# USB_Isolator_v001.net
KiCad netlist of a schematic drawn in EAGLE
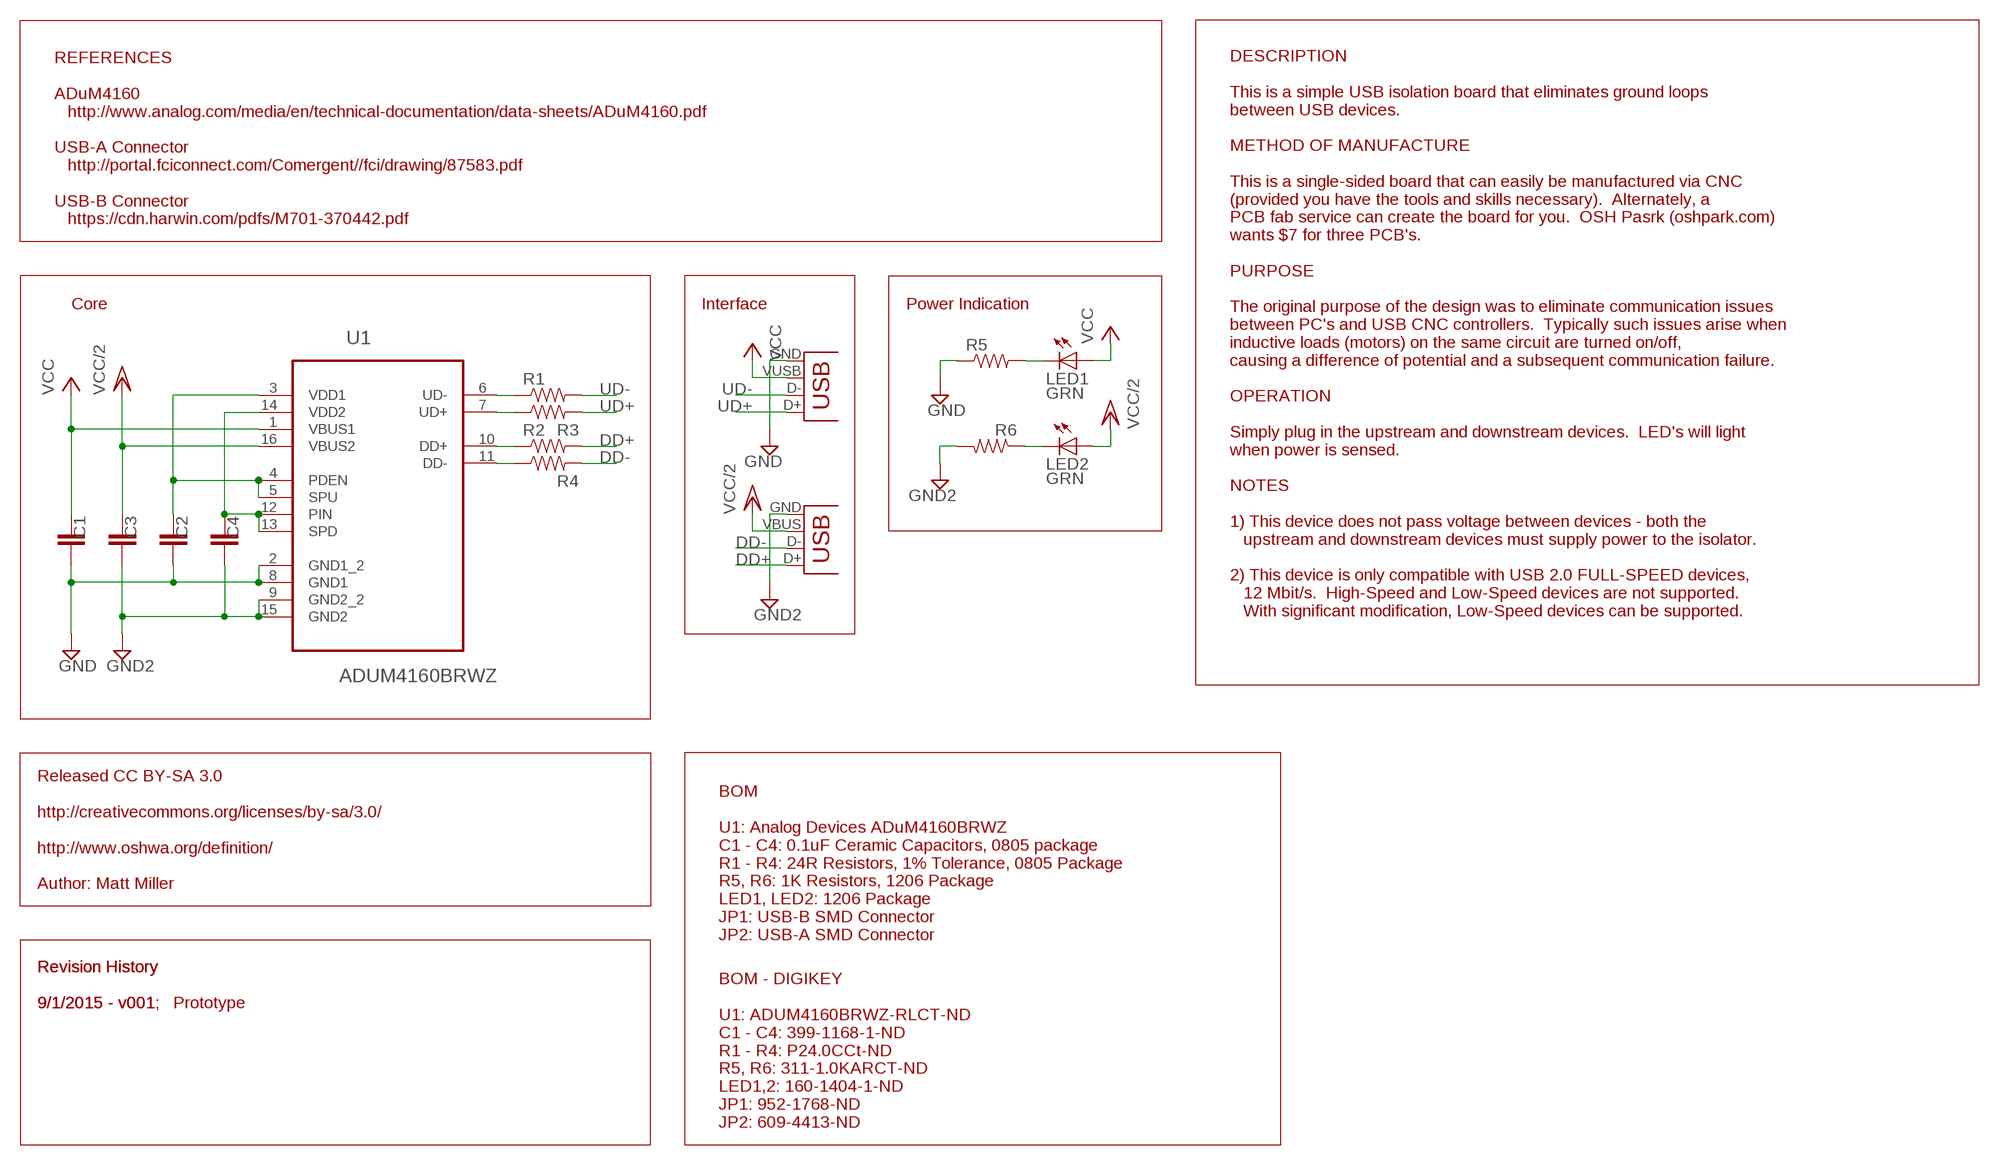
[diagram p0: schematic, sheet 1]

(export (version "E")
  (design (tool "Eeschema 10.0.6"))
  (components
    (comp (ref "C1")
      (value "0.1uF")
      (footprint "eagle-import:0805")
      (libsource (lib "eagle-import") (part "CAP0805"))
    )
    (comp (ref "C2")
      (value "0.1uF")
      (footprint "eagle-import:0805")
      (libsource (lib "eagle-import") (part "CAP0805"))
    )
    (comp (ref "C3")
      (value "0.1uF")
      (footprint "eagle-import:0805")
      (libsource (lib "eagle-import") (part "CAP0805"))
    )
    (comp (ref "C4")
      (value "0.1uF")
      (footprint "eagle-import:0805")
      (libsource (lib "eagle-import") (part "CAP0805"))
    )
    (comp (ref "JP1")
      (value "USB-B-S")
      (footprint "eagle-import:USB-B-SMT")
      (libsource (lib "eagle-import") (part "USB-B-S"))
    )
    (comp (ref "JP2")
      (value "USB-A-S")
      (footprint "eagle-import:USB-A-S")
      (libsource (lib "eagle-import") (part "USB-A-S"))
    )
    (comp (ref "LED1")
      (value "GRN")
      (footprint "eagle-import:LED-1206")
      (libsource (lib "eagle-import") (part "LED1206"))
    )
    (comp (ref "LED2")
      (value "GRN")
      (footprint "eagle-import:LED-1206")
      (libsource (lib "eagle-import") (part "LED1206"))
    )
    (comp (ref "R1")
      (value "25")
      (footprint "eagle-import:0805")
      (libsource (lib "eagle-import") (part "RESISTOR0805-RES"))
    )
    (comp (ref "R2")
      (value "25")
      (footprint "eagle-import:0805")
      (libsource (lib "eagle-import") (part "RESISTOR0805-RES"))
    )
    (comp (ref "R3")
      (value "25")
      (footprint "eagle-import:0805")
      (libsource (lib "eagle-import") (part "RESISTOR0805-RES"))
    )
    (comp (ref "R4")
      (value "25")
      (footprint "eagle-import:0805")
      (libsource (lib "eagle-import") (part "RESISTOR0805-RES"))
    )
    (comp (ref "R5")
      (value "1K")
      (footprint "eagle-import:1206")
      (libsource (lib "eagle-import") (part "SparkFun-Resistors_RESISTOR1206"))
    )
    (comp (ref "R6")
      (value "1K")
      (footprint "eagle-import:1206")
      (libsource (lib "eagle-import") (part "SparkFun-Resistors_RESISTOR1206"))
    )
    (comp (ref "U1")
      (value "ADUM4160BRWZ")
      (footprint "eagle-import:SOIC127P1032X265-16N")
      (libsource (lib "eagle-import") (part "ADUM4160BRWZ"))
    )
  )
  (nets
    (net (code "1") (name "/DD+") (class "Default")
      (node (ref "JP2") (pin "D+") (pinfunction "D+_D+") (pintype "bidirectional"))
      (node (ref "R4") (pin "2") (pinfunction "2_2") (pintype "passive"))
    )
    (net (code "2") (name "/DD-") (class "Default")
      (node (ref "JP2") (pin "D-") (pinfunction "D-_D-") (pintype "bidirectional"))
      (node (ref "R3") (pin "2") (pinfunction "2_2") (pintype "passive"))
    )
    (net (code "3") (name "/UD+") (class "Default")
      (node (ref "JP1") (pin "D+") (pinfunction "D+_D+") (pintype "bidirectional"))
      (node (ref "R2") (pin "2") (pinfunction "2_2") (pintype "passive"))
    )
    (net (code "4") (name "/UD-") (class "Default")
      (node (ref "JP1") (pin "D-") (pinfunction "D-_D-") (pintype "bidirectional"))
      (node (ref "R1") (pin "2") (pinfunction "2_2") (pintype "passive"))
    )
    (net (code "5") (name "GND") (class "Default")
      (node (ref "C1") (pin "2") (pinfunction "2_2") (pintype "passive"))
      (node (ref "C2") (pin "2") (pinfunction "2_2") (pintype "passive"))
      (node (ref "JP1") (pin "GND") (pinfunction "GND_GND") (pintype "bidirectional"))
      (node (ref "R5") (pin "1") (pinfunction "1_1") (pintype "passive"))
      (node (ref "U1") (pin "2") (pinfunction "GND1_2_2") (pintype "passive"))
      (node (ref "U1") (pin "8") (pinfunction "GND1_8") (pintype "passive"))
    )
    (net (code "6") (name "GND2") (class "Default")
      (node (ref "C3") (pin "2") (pinfunction "2_2") (pintype "passive"))
      (node (ref "C4") (pin "2") (pinfunction "2_2") (pintype "passive"))
      (node (ref "JP2") (pin "GND") (pinfunction "GND_GND") (pintype "bidirectional"))
      (node (ref "R6") (pin "2") (pinfunction "2_2") (pintype "passive"))
      (node (ref "U1") (pin "15") (pinfunction "GND2_15") (pintype "passive"))
      (node (ref "U1") (pin "9") (pinfunction "GND2_2_9") (pintype "passive"))
    )
    (net (code "7") (name "Net-(LED1-PadC)") (class "Default")
      (node (ref "LED1") (pin "C") (pinfunction "C_C") (pintype "passive"))
      (node (ref "R5") (pin "2") (pinfunction "2_2") (pintype "passive"))
    )
    (net (code "8") (name "Net-(LED2-PadC)") (class "Default")
      (node (ref "LED2") (pin "C") (pinfunction "C_C") (pintype "passive"))
      (node (ref "R6") (pin "1") (pinfunction "1_1") (pintype "passive"))
    )
    (net (code "9") (name "Net-(U1-DD+)") (class "Default")
      (node (ref "R4") (pin "1") (pinfunction "1_1") (pintype "passive"))
      (node (ref "U1") (pin "10") (pinfunction "DD+_10") (pintype "bidirectional"))
    )
    (net (code "10") (name "Net-(U1-DD-)") (class "Default")
      (node (ref "R3") (pin "1") (pinfunction "1_1") (pintype "passive"))
      (node (ref "U1") (pin "11") (pinfunction "DD-_11") (pintype "bidirectional"))
    )
    (net (code "11") (name "Net-(U1-PDEN)") (class "Default")
      (node (ref "C2") (pin "1") (pinfunction "1_1") (pintype "passive"))
      (node (ref "U1") (pin "3") (pinfunction "VDD1_3") (pintype "power_in"))
      (node (ref "U1") (pin "4") (pinfunction "PDEN_4") (pintype "input"))
      (node (ref "U1") (pin "5") (pinfunction "SPU_5") (pintype "input"))
    )
    (net (code "12") (name "Net-(U1-PIN)") (class "Default")
      (node (ref "C4") (pin "1") (pinfunction "1_1") (pintype "passive"))
      (node (ref "U1") (pin "12") (pinfunction "PIN_12") (pintype "input"))
      (node (ref "U1") (pin "13") (pinfunction "SPD_13") (pintype "input"))
      (node (ref "U1") (pin "14") (pinfunction "VDD2_14") (pintype "power_in"))
    )
    (net (code "13") (name "Net-(U1-UD+)") (class "Default")
      (node (ref "R2") (pin "1") (pinfunction "1_1") (pintype "passive"))
      (node (ref "U1") (pin "7") (pinfunction "UD+_7") (pintype "bidirectional"))
    )
    (net (code "14") (name "Net-(U1-UD-)") (class "Default")
      (node (ref "R1") (pin "1") (pinfunction "1_1") (pintype "passive"))
      (node (ref "U1") (pin "6") (pinfunction "UD-_6") (pintype "bidirectional"))
    )
    (net (code "15") (name "VCC") (class "Default")
      (node (ref "C1") (pin "1") (pinfunction "1_1") (pintype "passive"))
      (node (ref "JP1") (pin "VUSB") (pinfunction "VBUS_VUSB") (pintype "bidirectional"))
      (node (ref "LED1") (pin "A") (pinfunction "A_A") (pintype "passive"))
      (node (ref "U1") (pin "1") (pinfunction "VBUS1_1") (pintype "power_in"))
    )
    (net (code "16") (name "VCC{slash}2") (class "Default")
      (node (ref "C3") (pin "1") (pinfunction "1_1") (pintype "passive"))
      (node (ref "JP2") (pin "VBUS") (pinfunction "VBUS_VBUS") (pintype "bidirectional"))
      (node (ref "LED2") (pin "A") (pinfunction "A_A") (pintype "passive"))
      (node (ref "U1") (pin "16") (pinfunction "VBUS2_16") (pintype "power_in"))
    )
  )
)
